# Flash.net
KiCad netlist of a schematic drawn in Altium Designer
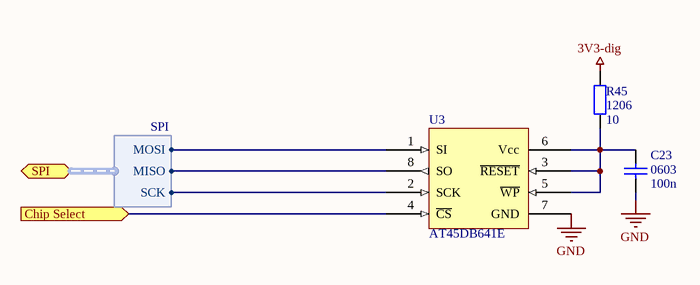
[diagram p0: Flash.SchDoc]

(export (version "E")
  (design (tool "Eeschema 10.0.6"))
  (components
    (comp (ref "C23")
      (value "0603")
      (footprint "SMD_Capacitor_0603")
      (description "Capacitor")
      (fields (field (name "ALTIUM_VALUE") "100n") (field (name "PUBLISHER") "Altium Limited"))
      (libsource (lib "Miscellaneous Devices") (part "Cap"))
    )
    (comp (ref "R45")
      (value "1206")
      (footprint "SMD_Resistor_1206")
      (description "Resistor")
      (fields (field (name "ALTIUM_VALUE") "10") (field (name "PUBLISHER") "Altium Limited"))
      (libsource (lib "Miscellaneous Devices") (part "Res2"))
    )
    (comp (ref "U3")
      (value "AT45DB641E")
      (footprint "SOIC-8-N")
      (description "64-Mbit DataFlash (with Extra 2-Mbits)")
      (libsource (lib "microcircuits_miscellaneous") (part "AT45DB641E"))
    )
  )
  (nets
    (net (code "2") (name "/Chip Select") (class "Default")
      (node (ref "U3") (pin "4") (pinfunction "~{CS}_4") (pintype "input"))
    )
    (net (code "3") (name "/MISO") (class "Default")
      (node (ref "U3") (pin "8") (pinfunction "SO_8") (pintype "output"))
    )
    (net (code "4") (name "/MOSI") (class "Default")
      (node (ref "U3") (pin "1") (pinfunction "SI_1") (pintype "input"))
    )
    (net (code "5") (name "/SCK") (class "Default")
      (node (ref "U3") (pin "2") (pinfunction "SCK_2") (pintype "input"))
    )
    (net (code "7") (name "3V3-dig") (class "Default")
      (node (ref "R45") (pin "1") (pinfunction "1_1") (pintype "passive"))
    )
    (net (code "8") (name "GND") (class "Default")
      (node (ref "C23") (pin "1") (pinfunction "1_1") (pintype "passive"))
      (node (ref "U3") (pin "7") (pinfunction "GND_7") (pintype "power_in"))
    )
    (net (code "9") (name "Net-(U3-Vcc)") (class "Default")
      (node (ref "C23") (pin "2") (pinfunction "2_2") (pintype "passive"))
      (node (ref "R45") (pin "2") (pinfunction "2_2") (pintype "passive"))
      (node (ref "U3") (pin "3") (pinfunction "~{RESET}_3") (pintype "input"))
      (node (ref "U3") (pin "5") (pinfunction "~{WP}_5") (pintype "input"))
      (node (ref "U3") (pin "6") (pinfunction "Vcc_6") (pintype "power_in"))
    )
  )
)
